# CAN.net
KiCad netlist of a schematic drawn in Altium Designer
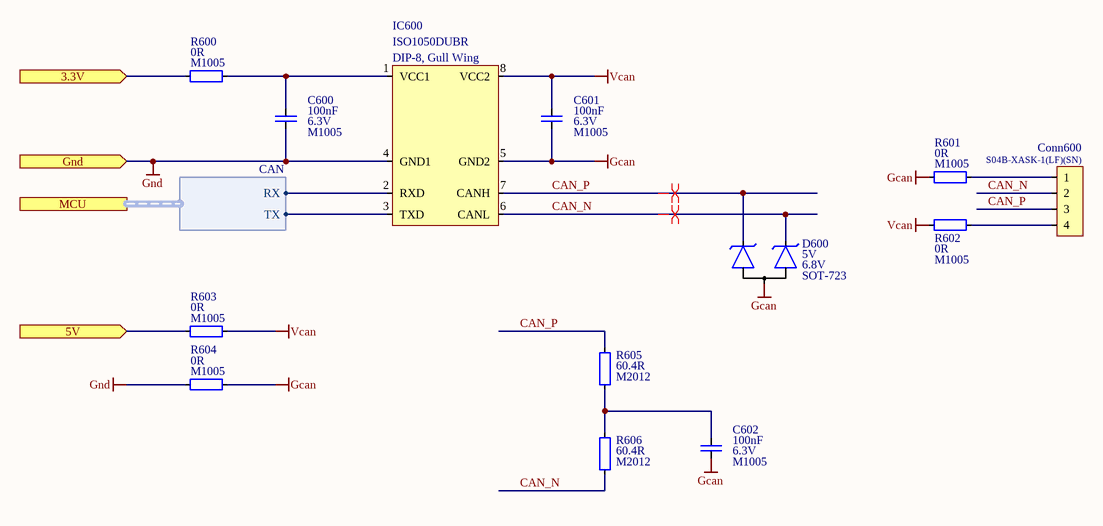
[diagram p0: CAN.SchDoc]

(export (version "E")
  (design (tool "Eeschema 10.0.6"))
  (components
    (comp (ref "C600")
      (value "100nF")
      (footprint "Capacitor_Ceramic_M1005_I0402")
      (description "Cap, Cer, 100nF, 6.3V, M1005")
      (fields
        (field (name "VOLTAGE") "6.3V")
        (field (name "MANUFACTURER PART NUMBER") "04026D104KAT4A")
        (field (name "MANUFACTURER") "Kyocera")
        (field (name "PACKAGE") "M1005")
      )
      (libsource (lib "Capacitor") (part "Capacitor_Ceramic"))
    )
    (comp (ref "C601")
      (value "100nF")
      (footprint "Capacitor_Ceramic_M1005_I0402")
      (description "Cap, Cer, 100nF, 6.3V, M1005")
      (fields
        (field (name "VOLTAGE") "6.3V")
        (field (name "MANUFACTURER PART NUMBER") "04026D104KAT4A")
        (field (name "MANUFACTURER") "Kyocera")
        (field (name "PACKAGE") "M1005")
      )
      (libsource (lib "Capacitor") (part "Capacitor_Ceramic"))
    )
    (comp (ref "C602")
      (value "100nF")
      (footprint "Capacitor_Ceramic_M1005_I0402")
      (description "Cap, Cer, 100nF, 6.3V, M1005")
      (fields
        (field (name "VOLTAGE") "6.3V")
        (field (name "MANUFACTURER PART NUMBER") "04026D104KAT4A")
        (field (name "MANUFACTURER") "Kyocera")
        (field (name "PACKAGE") "M1005")
      )
      (libsource (lib "Capacitor") (part "Capacitor_Ceramic"))
    )
    (comp (ref "Conn600")
      (value "Connector - 4P")
      (footprint "Connector, S04B-XASK-1")
      (description "Conn, JST, 4P, TH, XA, Side Entry")
      (fields
        (field (name "MANUFACTURER") "JST")
        (field (name "MANUFACTURER PART NUMBER") "S04B-XASK-1(LF)(SN)")
      )
      (libsource (lib "Connector - JST") (part "Connector - 4P"))
    )
    (comp (ref "D600")
      (value "Diode_Tvs_2P_Common_Anode")
      (footprint "Diode_SOT-723_2P_Common_Anode_Type_1")
      (description "Diode, TVS, 5V/6.8V, SOD-723")
      (fields
        (field (name "MANUFACTURER PART NUMBER") "DF3A6.8LFV,L3F")
        (field (name "MANUFACTURER") "Toshiba")
        (field (name "VOLTAGE, BREAK DOWN") "6.8V")
        (field (name "VOLTAGE, STAND OFF") "5V")
        (field (name "PACKAGE") "SOT-723")
      )
      (libsource (lib "Diode") (part "Diode_Tvs_2P_Common_Anode"))
    )
    (comp (ref "IC600")
      (value "CAN - Texas, ISO1050DUB")
      (footprint "DIP-8, Gull Wing")
      (description "IC, Interface, CAN, DIP-8, Gull Wing")
      (fields
        (field (name "MANUFACTURER") "Texas")
        (field (name "MANUFACTURER PART NUMBER") "ISO1050DUBR")
        (field (name "PACKAGE") "DIP-8, Gull Wing")
      )
      (libsource (lib "IC - Interface") (part "CAN - Texas, ISO1050DUB"))
    )
    (comp (ref "R600")
      (value "0R")
      (footprint "Resistor_Smd_M1005_I0402")
      (description "Res, 0R, M1005")
      (fields
        (field (name "MANUFACTURER") "Yageo")
        (field (name "MANUFACTURER PART NUMBER") "RC0402FR-070RL")
        (field (name "PACKAGE") "M1005")
      )
      (libsource (lib "Resistor") (part "Resistor"))
    )
    (comp (ref "R601")
      (value "0R")
      (footprint "Resistor_Smd_M1005_I0402")
      (description "Res, 0R, M1005")
      (fields
        (field (name "MANUFACTURER") "Yageo")
        (field (name "MANUFACTURER PART NUMBER") "RC0402FR-070RL")
        (field (name "PACKAGE") "M1005")
      )
      (libsource (lib "Resistor") (part "Resistor"))
    )
    (comp (ref "R602")
      (value "0R")
      (footprint "Resistor_Smd_M1005_I0402")
      (description "Res, 0R, M1005")
      (fields
        (field (name "MANUFACTURER") "Yageo")
        (field (name "MANUFACTURER PART NUMBER") "RC0402FR-070RL")
        (field (name "PACKAGE") "M1005")
      )
      (libsource (lib "Resistor") (part "Resistor"))
    )
    (comp (ref "R603")
      (value "0R")
      (footprint "Resistor_Smd_M1005_I0402")
      (description "Res, 0R, M1005")
      (fields
        (field (name "MANUFACTURER") "Yageo")
        (field (name "MANUFACTURER PART NUMBER") "RC0402FR-070RL")
        (field (name "PACKAGE") "M1005")
      )
      (libsource (lib "Resistor") (part "Resistor"))
    )
    (comp (ref "R604")
      (value "0R")
      (footprint "Resistor_Smd_M1005_I0402")
      (description "Res, 0R, M1005")
      (fields
        (field (name "MANUFACTURER") "Yageo")
        (field (name "MANUFACTURER PART NUMBER") "RC0402FR-070RL")
        (field (name "PACKAGE") "M1005")
      )
      (libsource (lib "Resistor") (part "Resistor"))
    )
    (comp (ref "R605")
      (value "60.4R")
      (footprint "Resistor_Smd_M2012_I0805")
      (description "Res, 60.4R, 1%, M1005")
      (fields
        (field (name "TOLERANCE") "1%")
        (field (name "MANUFACTURER") "Yageo")
        (field (name "PACKAGE") "M2012")
      )
      (libsource (lib "Resistor") (part "Resistor"))
    )
    (comp (ref "R606")
      (value "60.4R")
      (footprint "Resistor_Smd_M2012_I0805")
      (description "Res, 60.4R, 1%, M1005")
      (fields
        (field (name "TOLERANCE") "1%")
        (field (name "MANUFACTURER") "Yageo")
        (field (name "PACKAGE") "M2012")
      )
      (libsource (lib "Resistor") (part "Resistor"))
    )
  )
  (nets
    (net (code "2") (name "/3.3V") (class "Default")
      (node (ref "R600") (pin "1") (pinfunction "1_1") (pintype "passive"))
    )
    (net (code "3") (name "/5V") (class "Default")
      (node (ref "R603") (pin "1") (pinfunction "1_1") (pintype "passive"))
    )
    (net (code "4") (name "/CAN_N") (class "Default")
      (node (ref "Conn600") (pin "2") (pinfunction "2_2") (pintype "passive"))
      (node (ref "D600") (pin "C2") (pinfunction "C2_C2") (pintype "passive"))
      (node (ref "IC600") (pin "6") (pinfunction "CANL_6") (pintype "passive"))
      (node (ref "R606") (pin "2") (pinfunction "2_2") (pintype "passive"))
    )
    (net (code "5") (name "/CAN_P") (class "Default")
      (node (ref "Conn600") (pin "3") (pinfunction "3_3") (pintype "passive"))
      (node (ref "D600") (pin "C1") (pinfunction "C1_C1") (pintype "passive"))
      (node (ref "IC600") (pin "7") (pinfunction "CANH_7") (pintype "passive"))
      (node (ref "R605") (pin "1") (pinfunction "1_1") (pintype "passive"))
    )
    (net (code "6") (name "/RX") (class "Default")
      (node (ref "IC600") (pin "2") (pinfunction "RXD_2") (pintype "passive"))
    )
    (net (code "7") (name "/TX") (class "Default")
      (node (ref "IC600") (pin "3") (pinfunction "TXD_3") (pintype "passive"))
    )
    (net (code "9") (name "Gcan") (class "Default")
      (node (ref "C601") (pin "2") (pinfunction "2_2") (pintype "passive"))
      (node (ref "C602") (pin "2") (pinfunction "2_2") (pintype "passive"))
      (node (ref "D600") (pin "A") (pinfunction "A_A") (pintype "passive"))
      (node (ref "IC600") (pin "5") (pinfunction "GND2_5") (pintype "passive"))
      (node (ref "R601") (pin "1") (pinfunction "1_1") (pintype "passive"))
      (node (ref "R604") (pin "2") (pinfunction "2_2") (pintype "passive"))
    )
    (net (code "10") (name "Gnd") (class "Default")
      (node (ref "C600") (pin "2") (pinfunction "2_2") (pintype "passive"))
      (node (ref "IC600") (pin "4") (pinfunction "GND1_4") (pintype "passive"))
      (node (ref "R604") (pin "1") (pinfunction "1_1") (pintype "passive"))
    )
    (net (code "11") (name "Net-(C602-Pad1)") (class "Default")
      (node (ref "C602") (pin "1") (pinfunction "1_1") (pintype "passive"))
      (node (ref "R605") (pin "2") (pinfunction "2_2") (pintype "passive"))
      (node (ref "R606") (pin "1") (pinfunction "1_1") (pintype "passive"))
    )
    (net (code "12") (name "Net-(Conn600-Pad1)") (class "Default")
      (node (ref "Conn600") (pin "1") (pinfunction "1_1") (pintype "passive"))
      (node (ref "R601") (pin "2") (pinfunction "2_2") (pintype "passive"))
    )
    (net (code "13") (name "Net-(Conn600-Pad4)") (class "Default")
      (node (ref "Conn600") (pin "4") (pinfunction "4_4") (pintype "passive"))
      (node (ref "R602") (pin "2") (pinfunction "2_2") (pintype "passive"))
    )
    (net (code "14") (name "Net-(IC600-VCC1)") (class "Default")
      (node (ref "C600") (pin "1") (pinfunction "1_1") (pintype "passive"))
      (node (ref "IC600") (pin "1") (pinfunction "VCC1_1") (pintype "passive"))
      (node (ref "R600") (pin "2") (pinfunction "2_2") (pintype "passive"))
    )
    (net (code "15") (name "Vcan") (class "Default")
      (node (ref "C601") (pin "1") (pinfunction "1_1") (pintype "passive"))
      (node (ref "IC600") (pin "8") (pinfunction "VCC2_8") (pintype "passive"))
      (node (ref "R602") (pin "1") (pinfunction "1_1") (pintype "passive"))
      (node (ref "R603") (pin "2") (pinfunction "2_2") (pintype "passive"))
    )
  )
)
